# user_input_old.net
KiCad netlist of a schematic drawn in Altium Designer
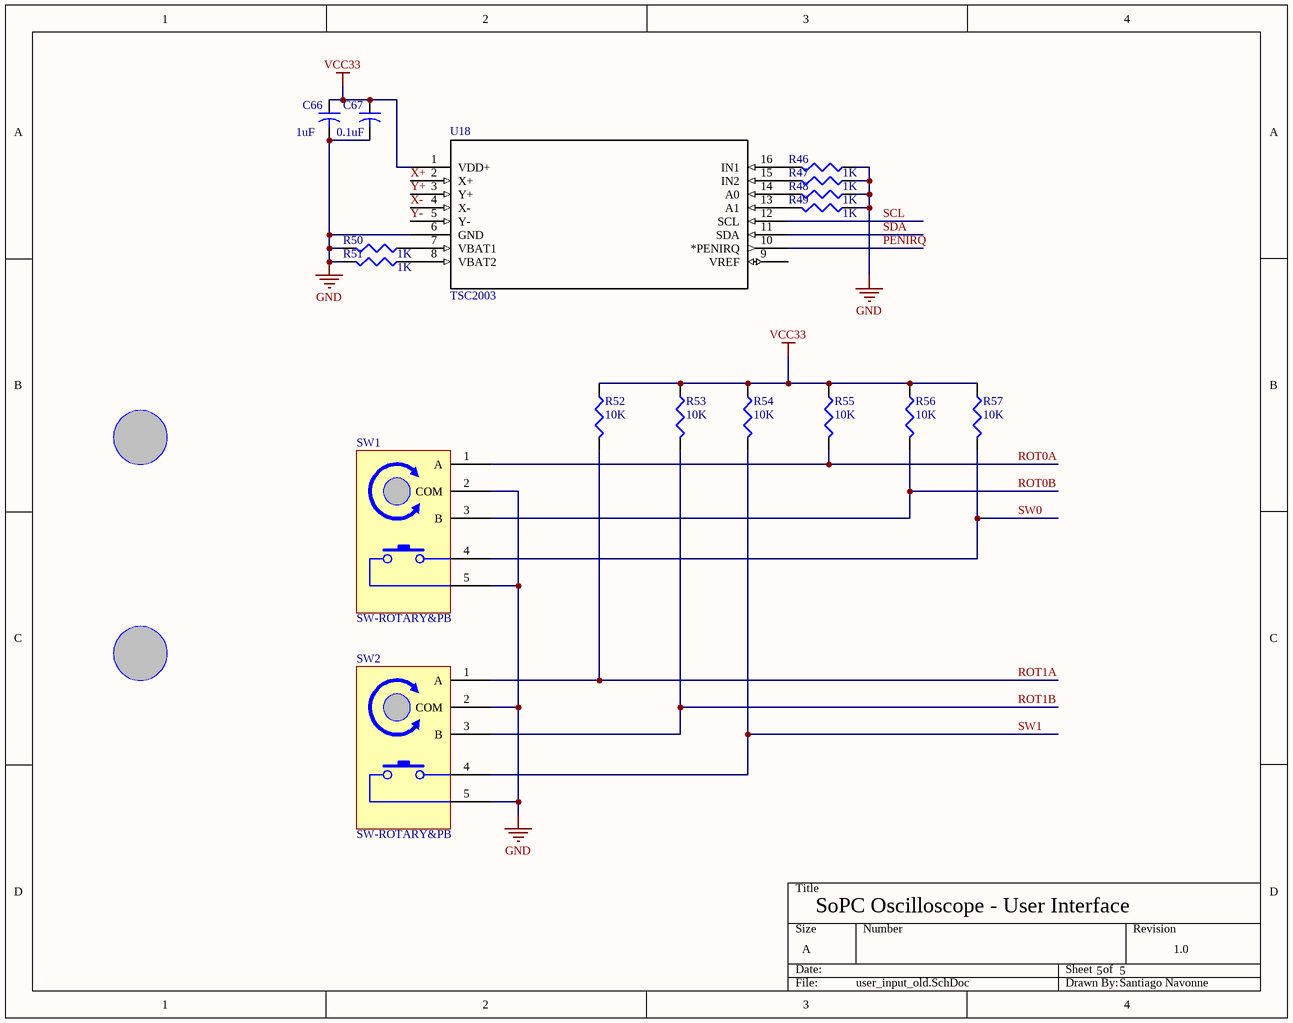
[diagram p0: user_input_old.SchDoc]

(export (version "E")
  (design (tool "Eeschema 10.0.6"))
  (components
    (comp (ref "C66")
      (value "1uF")
      (footprint "CAPC1608L")
      (description "Capacitor")
      (fields (field (name "Comment") "Cap2") (field (name "PUBLISHER") "Altium Limited"))
      (libsource (lib "Miscellaneous Devices") (part "Cap2"))
    )
    (comp (ref "C67")
      (value "0.1uF")
      (footprint "CAPC1608L")
      (description "Capacitor")
      (fields (field (name "Comment") "Cap2") (field (name "PUBLISHER") "Altium Limited"))
      (libsource (lib "Miscellaneous Devices") (part "Cap2"))
    )
    (comp (ref "R46")
      (value "1K")
      (footprint "RESC1608N")
      (description "Resistor")
      (fields (field (name "Comment") "Res3") (field (name "PUBLISHER") "Altium Limited"))
      (libsource (lib "Miscellaneous Devices") (part "Res3"))
    )
    (comp (ref "R47")
      (value "1K")
      (footprint "RESC1608N")
      (description "Resistor")
      (fields (field (name "Comment") "Res3") (field (name "PUBLISHER") "Altium Limited"))
      (libsource (lib "Miscellaneous Devices") (part "Res3"))
    )
    (comp (ref "R48")
      (value "1K")
      (footprint "RESC1608N")
      (description "Resistor")
      (fields (field (name "Comment") "Res3") (field (name "PUBLISHER") "Altium Limited"))
      (libsource (lib "Miscellaneous Devices") (part "Res3"))
    )
    (comp (ref "R49")
      (value "1K")
      (footprint "RESC1608N")
      (description "Resistor")
      (fields (field (name "Comment") "Res3") (field (name "PUBLISHER") "Altium Limited"))
      (libsource (lib "Miscellaneous Devices") (part "Res3"))
    )
    (comp (ref "R50")
      (value "1K")
      (footprint "RESC1608N")
      (description "Resistor")
      (fields (field (name "Comment") "Res3") (field (name "PUBLISHER") "Altium Limited"))
      (libsource (lib "Miscellaneous Devices") (part "Res3"))
    )
    (comp (ref "R51")
      (value "1K")
      (footprint "RESC1608N")
      (description "Resistor")
      (fields (field (name "Comment") "Res3") (field (name "PUBLISHER") "Altium Limited"))
      (libsource (lib "Miscellaneous Devices") (part "Res3"))
    )
    (comp (ref "R52")
      (value "10K")
      (footprint "RESC1608N")
      (description "Resistor")
      (fields (field (name "Comment") "Res3") (field (name "PUBLISHER") "Altium Limited"))
      (libsource (lib "Miscellaneous Devices") (part "Res3"))
    )
    (comp (ref "R53")
      (value "10K")
      (footprint "RESC1608N")
      (description "Resistor")
      (fields (field (name "Comment") "Res3") (field (name "PUBLISHER") "Altium Limited"))
      (libsource (lib "Miscellaneous Devices") (part "Res3"))
    )
    (comp (ref "R54")
      (value "10K")
      (footprint "RESC1608N")
      (description "Resistor")
      (fields (field (name "Comment") "Res3") (field (name "PUBLISHER") "Altium Limited"))
      (libsource (lib "Miscellaneous Devices") (part "Res3"))
    )
    (comp (ref "R55")
      (value "10K")
      (footprint "RESC1608N")
      (description "Resistor")
      (fields (field (name "Comment") "Res3") (field (name "PUBLISHER") "Altium Limited"))
      (libsource (lib "Miscellaneous Devices") (part "Res3"))
    )
    (comp (ref "R56")
      (value "10K")
      (footprint "RESC1608N")
      (description "Resistor")
      (fields (field (name "Comment") "Res3") (field (name "PUBLISHER") "Altium Limited"))
      (libsource (lib "Miscellaneous Devices") (part "Res3"))
    )
    (comp (ref "R57")
      (value "10K")
      (footprint "RESC1608N")
      (description "Resistor")
      (fields (field (name "Comment") "Res3") (field (name "PUBLISHER") "Altium Limited"))
      (libsource (lib "Miscellaneous Devices") (part "Res3"))
    )
    (comp (ref "SW1")
      (value "SW-ROTARY&PB")
      (footprint "PEC16-4xxxF-Sxxxx")
      (description "Rotary Encoder with Built-In Push Button")
      (libsource (lib "EECS5X") (part "SW-ROTARY&PB"))
    )
    (comp (ref "SW2")
      (value "SW-ROTARY&PB")
      (footprint "PEC16-4xxxF-Sxxxx")
      (description "Rotary Encoder with Built-In Push Button")
      (libsource (lib "EECS5X") (part "SW-ROTARY&PB"))
    )
    (comp (ref "U18")
      (value "TSC2003")
      (footprint "PW16")
      (description "Imported")
      (fields (field (name "MANUFACTURER") "Texas Instruments"))
      (libsource (lib "2014-02-05_22-29-57") (part "TSC2003_PW_16"))
    )
  )
  (nets
    (net (code "1") (name "/PENIRQ") (class "Default")
      (node (ref "U18") (pin "10") (pinfunction "*PENIRQ_10") (pintype "output"))
    )
    (net (code "2") (name "/ROT0A") (class "Default")
      (node (ref "R55") (pin "2") (pinfunction "2_2") (pintype "passive"))
      (node (ref "SW1") (pin "1") (pinfunction "A_1") (pintype "passive"))
    )
    (net (code "3") (name "/ROT0B") (class "Default")
      (node (ref "R56") (pin "2") (pinfunction "2_2") (pintype "passive"))
      (node (ref "SW1") (pin "3") (pinfunction "B_3") (pintype "passive"))
    )
    (net (code "4") (name "/ROT1A") (class "Default")
      (node (ref "R52") (pin "2") (pinfunction "2_2") (pintype "passive"))
      (node (ref "SW2") (pin "1") (pinfunction "A_1") (pintype "passive"))
    )
    (net (code "5") (name "/ROT1B") (class "Default")
      (node (ref "R53") (pin "2") (pinfunction "2_2") (pintype "passive"))
      (node (ref "SW2") (pin "3") (pinfunction "B_3") (pintype "passive"))
    )
    (net (code "6") (name "/SCL") (class "Default")
      (node (ref "U18") (pin "12") (pinfunction "SCL_12") (pintype "input"))
    )
    (net (code "7") (name "/SDA") (class "Default")
      (node (ref "U18") (pin "11") (pinfunction "SDA_11") (pintype "input"))
    )
    (net (code "8") (name "/SW0") (class "Default")
      (node (ref "R57") (pin "2") (pinfunction "2_2") (pintype "passive"))
      (node (ref "SW1") (pin "4") (pintype "passive"))
    )
    (net (code "9") (name "/SW1") (class "Default")
      (node (ref "R54") (pin "2") (pinfunction "2_2") (pintype "passive"))
      (node (ref "SW2") (pin "4") (pintype "passive"))
    )
    (net (code "10") (name "/X+") (class "Default")
      (node (ref "U18") (pin "2") (pinfunction "X+_2") (pintype "input"))
    )
    (net (code "11") (name "/X-") (class "Default")
      (node (ref "U18") (pin "4") (pinfunction "X-_4") (pintype "input"))
    )
    (net (code "12") (name "/Y+") (class "Default")
      (node (ref "U18") (pin "3") (pinfunction "Y+_3") (pintype "input"))
    )
    (net (code "13") (name "/Y-") (class "Default")
      (node (ref "U18") (pin "5") (pinfunction "Y-_5") (pintype "input"))
    )
    (net (code "14") (name "GND") (class "Default")
      (node (ref "C66") (pin "2") (pinfunction "2_2") (pintype "passive"))
      (node (ref "C67") (pin "2") (pinfunction "2_2") (pintype "passive"))
      (node (ref "R46") (pin "1") (pinfunction "1_1") (pintype "passive"))
      (node (ref "R47") (pin "1") (pinfunction "1_1") (pintype "passive"))
      (node (ref "R48") (pin "1") (pinfunction "1_1") (pintype "passive"))
      (node (ref "R49") (pin "1") (pinfunction "1_1") (pintype "passive"))
      (node (ref "R50") (pin "2") (pinfunction "2_2") (pintype "passive"))
      (node (ref "R51") (pin "2") (pinfunction "2_2") (pintype "passive"))
      (node (ref "SW1") (pin "2") (pinfunction "COM_2") (pintype "passive"))
      (node (ref "SW1") (pin "5") (pintype "passive"))
      (node (ref "SW2") (pin "2") (pinfunction "COM_2") (pintype "passive"))
      (node (ref "SW2") (pin "5") (pintype "passive"))
      (node (ref "U18") (pin "6") (pinfunction "GND_6") (pintype "power_in"))
    )
    (net (code "15") (name "Net-(U18-A0)") (class "Default")
      (node (ref "R48") (pin "2") (pinfunction "2_2") (pintype "passive"))
      (node (ref "U18") (pin "14") (pinfunction "A0_14") (pintype "input"))
    )
    (net (code "16") (name "Net-(U18-A1)") (class "Default")
      (node (ref "R49") (pin "2") (pinfunction "2_2") (pintype "passive"))
      (node (ref "U18") (pin "13") (pinfunction "A1_13") (pintype "input"))
    )
    (net (code "17") (name "Net-(U18-IN1)") (class "Default")
      (node (ref "R46") (pin "2") (pinfunction "2_2") (pintype "passive"))
      (node (ref "U18") (pin "16") (pinfunction "IN1_16") (pintype "input"))
    )
    (net (code "18") (name "Net-(U18-IN2)") (class "Default")
      (node (ref "R47") (pin "2") (pinfunction "2_2") (pintype "passive"))
      (node (ref "U18") (pin "15") (pinfunction "IN2_15") (pintype "input"))
    )
    (net (code "19") (name "Net-(U18-VBAT1)") (class "Default")
      (node (ref "R50") (pin "1") (pinfunction "1_1") (pintype "passive"))
      (node (ref "U18") (pin "7") (pinfunction "VBAT1_7") (pintype "input"))
    )
    (net (code "20") (name "Net-(U18-VBAT2)") (class "Default")
      (node (ref "R51") (pin "1") (pinfunction "1_1") (pintype "passive"))
      (node (ref "U18") (pin "8") (pinfunction "VBAT2_8") (pintype "input"))
    )
    (net (code "21") (name "VCC33") (class "Default")
      (node (ref "C66") (pin "1") (pinfunction "1_1") (pintype "passive"))
      (node (ref "C67") (pin "1") (pinfunction "1_1") (pintype "passive"))
      (node (ref "R52") (pin "1") (pinfunction "1_1") (pintype "passive"))
      (node (ref "R53") (pin "1") (pinfunction "1_1") (pintype "passive"))
      (node (ref "R54") (pin "1") (pinfunction "1_1") (pintype "passive"))
      (node (ref "R55") (pin "1") (pinfunction "1_1") (pintype "passive"))
      (node (ref "R56") (pin "1") (pinfunction "1_1") (pintype "passive"))
      (node (ref "R57") (pin "1") (pinfunction "1_1") (pintype "passive"))
      (node (ref "U18") (pin "1") (pinfunction "VDD+_1") (pintype "power_in"))
    )
    (net (code "22") (name "unconnected-(U18-VREF-Pad9)") (class "Default")
      (node (ref "U18") (pin "9") (pinfunction "VREF_9") (pintype "bidirectional"))
    )
  )
)
